# main.net
KiCad netlist of a schematic drawn in EAGLE
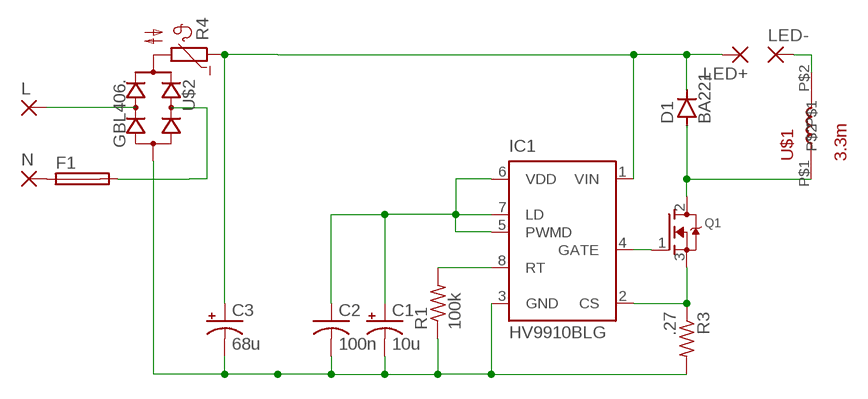
[diagram p0: schematic, sheet 1]

(export (version "E")
  (design (tool "Eeschema 10.0.6"))
  (components
    (comp (ref "C1")
      (value "10u")
      (footprint "eagle-import:CT7343")
      (libsource (lib "eagle-import") (part "CPOL-USCT7343"))
    )
    (comp (ref "C2")
      (value "100n")
      (footprint "eagle-import:C0603")
      (libsource (lib "eagle-import") (part "C-USC0603"))
    )
    (comp (ref "C3")
      (value "68u")
      (footprint "eagle-import:E7,5-16")
      (libsource (lib "eagle-import") (part "CPOL-USE7.5-16"))
    )
    (comp (ref "D1")
      (value "BA221")
      (footprint "eagle-import:DO35-10")
      (libsource (lib "eagle-import") (part "BA221"))
    )
    (comp (ref "F1")
      (value "SH22,5A")
      (footprint "eagle-import:SH22,5A")
      (fields (field (name "MPN") "0031.7701.11"))
      (libsource (lib "eagle-import") (part "SH22,5A"))
    )
    (comp (ref "IC1")
      (value "HV9910BLG")
      (footprint "eagle-import:SOIC-08LG")
      (fields (field (name "MPN") "MXHV9910B"))
      (libsource (lib "eagle-import") (part "HV9910BLG"))
    )
    (comp (ref "L")
      (value "2,54/1,0")
      (footprint "eagle-import:2,54_1,0")
      (libsource (lib "eagle-import") (part "2,54/1,0"))
    )
    (comp (ref "LED+")
      (value "2,54/1,0")
      (footprint "eagle-import:2,54_1,0")
      (libsource (lib "eagle-import") (part "2,54/1,0"))
    )
    (comp (ref "LED-")
      (value "2,54/1,0")
      (footprint "eagle-import:2,54_1,0")
      (libsource (lib "eagle-import") (part "2,54/1,0"))
    )
    (comp (ref "N")
      (value "2,54/1,0")
      (footprint "eagle-import:2,54_1,0")
      (libsource (lib "eagle-import") (part "2,54/1,0"))
    )
    (comp (ref "Q1")
      (value "MOSFET-NGDS_TO220V")
      (footprint "eagle-import:TO220V")
      (libsource (lib "eagle-import") (part "MOSFET-NGDS_TO220V"))
    )
    (comp (ref "R1")
      (value "100k")
      (footprint "eagle-import:R0805")
      (libsource (lib "eagle-import") (part "R-US_R0805"))
    )
    (comp (ref "R3")
      (value ".27")
      (footprint "eagle-import:0207_7")
      (libsource (lib "eagle-import") (part "R-US_0207/7"))
    )
    (comp (ref "R4")
      (value "B57164")
      (footprint "eagle-import:B57164")
      (fields (field (name "MPN") "B57164K474K52"))
      (libsource (lib "eagle-import") (part "B57164"))
    )
    (comp (ref "U$1")
      (value "3.3m")
      (footprint "eagle-import:3.3MH")
      (libsource (lib "eagle-import") (part "3.3MH"))
    )
    (comp (ref "U$2")
      (value "GBL406.")
      (footprint "eagle-import:GBL406")
      (libsource (lib "eagle-import") (part "GBL406."))
    )
  )
  (nets
    (net (code "1") (name "Net-(F1-Pad2)") (class "Default")
      (node (ref "F1") (pin "2") (pinfunction "2_2") (pintype "passive"))
      (node (ref "U$2") (pin "AC@1") (pinfunction "AC_AC@1") (pintype "passive"))
    )
    (net (code "2") (name "Net-(IC1-CS)") (class "Default")
      (node (ref "IC1") (pin "2") (pinfunction "CS_2") (pintype "input"))
      (node (ref "Q1") (pin "3") (pinfunction "S_3") (pintype "bidirectional"))
      (node (ref "R3") (pin "1") (pinfunction "1_1") (pintype "passive"))
    )
    (net (code "3") (name "Net-(IC1-GATE)") (class "Default")
      (node (ref "IC1") (pin "4") (pinfunction "GATE_4") (pintype "output"))
      (node (ref "Q1") (pin "1") (pinfunction "G_1") (pintype "bidirectional"))
    )
    (net (code "4") (name "Net-(IC1-GND)") (class "Default")
      (node (ref "C1") (pin "-") (pinfunction "-_-") (pintype "passive"))
      (node (ref "C2") (pin "2") (pinfunction "2_2") (pintype "passive"))
      (node (ref "C3") (pin "-") (pinfunction "-_-") (pintype "passive"))
      (node (ref "IC1") (pin "3") (pinfunction "GND_3") (pintype "power_in"))
      (node (ref "R1") (pin "1") (pinfunction "1_1") (pintype "passive"))
      (node (ref "R3") (pin "2") (pinfunction "2_2") (pintype "passive"))
      (node (ref "U$2") (pin "-") (pinfunction "-_-") (pintype "passive"))
    )
    (net (code "5") (name "Net-(IC1-LD)") (class "Default")
      (node (ref "C1") (pin "+") (pinfunction "+_+") (pintype "passive"))
      (node (ref "C2") (pin "1") (pinfunction "1_1") (pintype "passive"))
      (node (ref "IC1") (pin "5") (pinfunction "PWMD_5") (pintype "input"))
      (node (ref "IC1") (pin "6") (pinfunction "VDD_6") (pintype "power_in"))
      (node (ref "IC1") (pin "7") (pinfunction "LD_7") (pintype "input"))
    )
    (net (code "6") (name "Net-(IC1-RT)") (class "Default")
      (node (ref "IC1") (pin "8") (pinfunction "RT_8") (pintype "passive"))
      (node (ref "R1") (pin "2") (pinfunction "2_2") (pintype "passive"))
    )
    (net (code "7") (name "Net-(IC1-VIN)") (class "Default")
      (node (ref "C3") (pin "+") (pinfunction "+_+") (pintype "passive"))
      (node (ref "D1") (pin "C") (pinfunction "C_C") (pintype "passive"))
      (node (ref "IC1") (pin "1") (pinfunction "VIN_1") (pintype "input"))
      (node (ref "LED+") (pin "1") (pinfunction "P_1") (pintype "passive"))
      (node (ref "R4") (pin "1") (pinfunction "1_1") (pintype "passive"))
    )
    (net (code "8") (name "Net-(L-P)") (class "Default")
      (node (ref "L") (pin "1") (pinfunction "P_1") (pintype "passive"))
      (node (ref "U$2") (pin "AC@2") (pinfunction "AC_AC@2") (pintype "passive"))
    )
    (net (code "9") (name "Net-(LED--P)") (class "Default")
      (node (ref "LED-") (pin "1") (pinfunction "P_1") (pintype "passive"))
      (node (ref "U$1") (pin "P$2") (pinfunction "P$2_P$2") (pintype "bidirectional"))
    )
    (net (code "10") (name "Net-(N-P)") (class "Default")
      (node (ref "F1") (pin "1") (pinfunction "1_1") (pintype "passive"))
      (node (ref "N") (pin "1") (pinfunction "P_1") (pintype "passive"))
    )
    (net (code "11") (name "Net-(Q1-D)") (class "Default")
      (node (ref "D1") (pin "A") (pinfunction "A_A") (pintype "passive"))
      (node (ref "Q1") (pin "2") (pinfunction "D_2") (pintype "bidirectional"))
      (node (ref "U$1") (pin "P$1") (pinfunction "P$1_P$1") (pintype "bidirectional"))
    )
    (net (code "12") (name "Net-(R4-Pad2)") (class "Default")
      (node (ref "R4") (pin "2") (pinfunction "2_2") (pintype "passive"))
      (node (ref "U$2") (pin "+") (pinfunction "+_+") (pintype "passive"))
    )
  )
)
